# navBoard.net
KiCad netlist of a schematic drawn in EAGLE
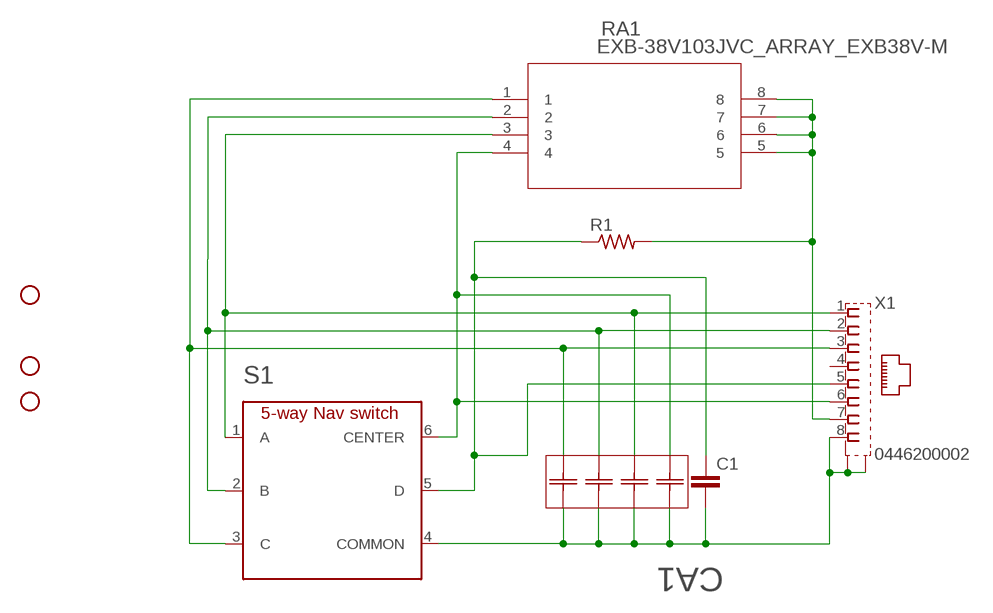
[diagram p0: schematic, sheet 1]

(export (version "E")
  (design (tool "Eeschema 10.0.6"))
  (components
    (comp (ref "C1")
      (value "C-EUC0603K")
      (footprint "eagle-import:C0603K")
      (libsource (lib "eagle-import") (part "C-EUC0603K"))
    )
    (comp (ref "CA1")
      (value "CKCL44X5R0J104M085AACKCL44-M")
      (footprint "eagle-import:CKCL44-M")
      (fields (field (name "MANUFACTURER_PART_NUMBER") "CKCL44X5R0J104M085AA"))
      (libsource (lib "eagle-import") (part "CKCL44X5R0J104M085AACKCL44-M"))
    )
    (comp (ref "H1")
      (value "STAND-OFF")
      (footprint "eagle-import:STAND-OFF")
      (libsource (lib "eagle-import") (part "STAND-OFF"))
    )
    (comp (ref "H2")
      (value "STAND-OFF")
      (footprint "eagle-import:STAND-OFF")
      (libsource (lib "eagle-import") (part "STAND-OFF"))
    )
    (comp (ref "H4")
      (value "STAND-OFF")
      (footprint "eagle-import:STAND-OFF")
      (libsource (lib "eagle-import") (part "STAND-OFF"))
    )
    (comp (ref "R1")
      (value "R-US_R0603")
      (footprint "eagle-import:R0603")
      (libsource (lib "eagle-import") (part "R-US_R0603"))
    )
    (comp (ref "RA1")
      (value "EXB-38V103JVC_ARRAY_EXB38V-M")
      (footprint "eagle-import:C_ARRAY_EXB38V-M")
      (fields (field (name "MANUFACTURER_PART_NUMBER") "EXB38V103JV"))
      (libsource (lib "eagle-import") (part "EXB-38V103JVC_ARRAY_EXB38V-M"))
    )
    (comp (ref "S1")
      (value "SKQUCAA010")
      (footprint "eagle-import:SKQUCAA010")
      (libsource (lib "eagle-import") (part "SKQUCAA010"))
    )
    (comp (ref "X1")
      (value "0446200002")
      (footprint "eagle-import:0446200002")
      (fields (field (name "MF") "MOLEX"))
      (libsource (lib "eagle-import") (part "0446200002"))
    )
  )
  (nets
    (net (code "1") (name "Net-(CA1-17)") (class "Default")
      (node (ref "CA1") (pin "1") (pinfunction "17_1") (pintype "passive"))
      (node (ref "RA1") (pin "4") (pinfunction "4_4") (pintype "passive"))
      (node (ref "S1") (pin "6") (pinfunction "CENTER_6") (pintype "bidirectional"))
      (node (ref "X1") (pin "6") (pinfunction "6_6") (pintype "passive"))
    )
    (net (code "2") (name "Net-(CA1-25)") (class "Default")
      (node (ref "CA1") (pin "2") (pinfunction "25_2") (pintype "passive"))
      (node (ref "RA1") (pin "3") (pinfunction "3_3") (pintype "passive"))
      (node (ref "S1") (pin "1") (pinfunction "A_1") (pintype "bidirectional"))
      (node (ref "X1") (pin "1") (pinfunction "1_1") (pintype "passive"))
    )
    (net (code "3") (name "Net-(CA1-33)") (class "Default")
      (node (ref "CA1") (pin "3") (pinfunction "33_3") (pintype "passive"))
      (node (ref "RA1") (pin "2") (pinfunction "2_2") (pintype "passive"))
      (node (ref "S1") (pin "2") (pinfunction "B_2") (pintype "bidirectional"))
      (node (ref "X1") (pin "2") (pinfunction "2_2") (pintype "passive"))
    )
    (net (code "4") (name "Net-(CA1-41)") (class "Default")
      (node (ref "CA1") (pin "4") (pinfunction "41_4") (pintype "passive"))
      (node (ref "RA1") (pin "1") (pinfunction "1_1") (pintype "passive"))
      (node (ref "S1") (pin "3") (pinfunction "C_3") (pintype "bidirectional"))
      (node (ref "X1") (pin "3") (pinfunction "3_3") (pintype "passive"))
    )
    (net (code "5") (name "Net-(CA1-52)") (class "Default")
      (node (ref "C1") (pin "2") (pinfunction "2_2") (pintype "passive"))
      (node (ref "CA1") (pin "5") (pinfunction "52_5") (pintype "passive"))
      (node (ref "CA1") (pin "6") (pinfunction "64_6") (pintype "passive"))
      (node (ref "CA1") (pin "7") (pinfunction "76_7") (pintype "passive"))
      (node (ref "CA1") (pin "8") (pinfunction "88_8") (pintype "passive"))
      (node (ref "S1") (pin "4") (pinfunction "COMMON_4") (pintype "power_in"))
      (node (ref "X1") (pin "8") (pinfunction "8_8") (pintype "passive"))
      (node (ref "X1") (pin "S@1") (pinfunction "S1_S@1") (pintype "passive"))
      (node (ref "X1") (pin "S@2") (pinfunction "S2_S@2") (pintype "passive"))
    )
    (net (code "6") (name "Net-(R1-Pad2)") (class "Default")
      (node (ref "R1") (pin "2") (pinfunction "2_2") (pintype "passive"))
      (node (ref "RA1") (pin "5") (pinfunction "5_5") (pintype "passive"))
      (node (ref "RA1") (pin "6") (pinfunction "6_6") (pintype "passive"))
      (node (ref "RA1") (pin "7") (pinfunction "7_7") (pintype "passive"))
      (node (ref "RA1") (pin "8") (pinfunction "8_8") (pintype "passive"))
      (node (ref "X1") (pin "7") (pinfunction "7_7") (pintype "passive"))
    )
    (net (code "7") (name "Net-(S1-D)") (class "Default")
      (node (ref "C1") (pin "1") (pinfunction "1_1") (pintype "passive"))
      (node (ref "R1") (pin "1") (pinfunction "1_1") (pintype "passive"))
      (node (ref "S1") (pin "5") (pinfunction "D_5") (pintype "bidirectional"))
      (node (ref "X1") (pin "5") (pinfunction "5_5") (pintype "passive"))
    )
    (net (code "8") (name "unconnected-(X1-Pad4)") (class "Default")
      (node (ref "X1") (pin "4") (pinfunction "4_4") (pintype "passive"))
    )
  )
)
